# design.net
KiCad netlist of a schematic drawn in Altium Designer
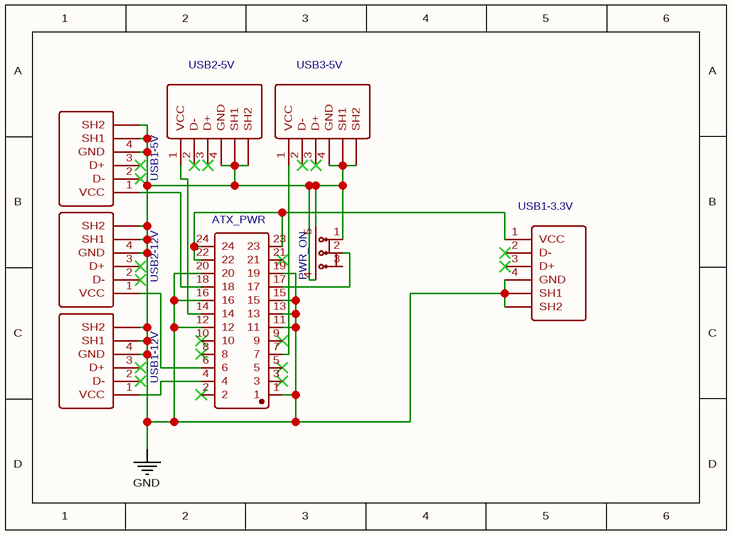
[diagram p0: 原理图.schdoc]

(export (version "E")
  (design (tool "Eeschema 10.0.6"))
  (components
    (comp (ref "ATX_PWR")
      (value "5557S-2*12P")
      (fields
        (field (name "BOM_MANUFACTURER PART") "W-5557S24P-0000")
        (field (name "BOM_SUPPLIER PART") "C169053")
        (field (name "CONTRIBUTOR") "LCSC")
      )
      (libsource (lib "altium-import") (part "root_2_5557S-2*12P_"))
    )
    (comp (ref "PWR_ON")
      (value "SS-12D02-VG4_C2998801")
      (fields
        (field (name "BOM_SUPPLIER PART") "C2998801")
        (field (name "BOM_MANUFACTURER PART") "SS-12D02-VG4")
        (field (name "CONTRIBUTOR") "lcsc")
      )
      (libsource (lib "altium-import") (part "root_3_SS-12D02-VG4_C2998801_"))
    )
    (comp (ref "USB1-3.3V")
      (value "U-USBAM04P-F001")
      (fields (field (name "BOM_SUPPLIER PART") "C2895042") (field (name "CONTRIBUTOR") "LCSC"))
      (libsource (lib "altium-import") (part "root_0_U-USBAM04P-F001_"))
    )
    (comp (ref "USB1-5V")
      (value "U-USBAM04P-F001")
      (fields (field (name "BOM_SUPPLIER PART") "C2895042") (field (name "CONTRIBUTOR") "LCSC"))
      (libsource (lib "altium-import") (part "root_2_U-USBAM04P-F001_"))
    )
    (comp (ref "USB1-12V")
      (value "U-USBAM04P-F001")
      (fields (field (name "BOM_SUPPLIER PART") "C2895042") (field (name "CONTRIBUTOR") "LCSC"))
      (libsource (lib "altium-import") (part "root_2_U-USBAM04P-F001_"))
    )
    (comp (ref "USB2-5V")
      (value "U-USBAM04P-F001")
      (fields (field (name "BOM_SUPPLIER PART") "C2895042") (field (name "CONTRIBUTOR") "LCSC"))
      (libsource (lib "altium-import") (part "root_1_U-USBAM04P-F001_"))
    )
    (comp (ref "USB2-12V")
      (value "U-USBAM04P-F001")
      (fields (field (name "BOM_SUPPLIER PART") "C2895042") (field (name "CONTRIBUTOR") "LCSC"))
      (libsource (lib "altium-import") (part "root_2_U-USBAM04P-F001_"))
    )
    (comp (ref "USB3-5V")
      (value "U-USBAM04P-F001")
      (fields (field (name "BOM_SUPPLIER PART") "C2895042") (field (name "CONTRIBUTOR") "LCSC"))
      (libsource (lib "altium-import") (part "root_1_U-USBAM04P-F001_"))
    )
  )
  (nets
    (net (code "1") (name "GND") (class "Default")
      (node (ref "ATX_PWR") (pin "1") (pinfunction "1_1") (pintype "passive"))
      (node (ref "ATX_PWR") (pin "11") (pinfunction "11_11") (pintype "passive"))
      (node (ref "ATX_PWR") (pin "12") (pinfunction "12_12") (pintype "passive"))
      (node (ref "ATX_PWR") (pin "13") (pinfunction "13_13") (pintype "passive"))
      (node (ref "ATX_PWR") (pin "15") (pinfunction "15_15") (pintype "passive"))
      (node (ref "ATX_PWR") (pin "16") (pinfunction "16_16") (pintype "passive"))
      (node (ref "ATX_PWR") (pin "19") (pinfunction "19_19") (pintype "passive"))
      (node (ref "ATX_PWR") (pin "20") (pinfunction "20_20") (pintype "passive"))
      (node (ref "PWR_ON") (pin "1") (pinfunction "1_1") (pintype "passive"))
      (node (ref "PWR_ON") (pin "4") (pinfunction "4_4") (pintype "passive"))
      (node (ref "PWR_ON") (pin "5") (pinfunction "5_5") (pintype "passive"))
      (node (ref "USB1-12V") (pin "4") (pinfunction "GND_4") (pintype "passive"))
      (node (ref "USB1-12V") (pin "SH1") (pinfunction "SH1_SH1") (pintype "passive"))
      (node (ref "USB1-12V") (pin "SH2") (pinfunction "SH2_SH2") (pintype "passive"))
      (node (ref "USB1-3.3V") (pin "4") (pinfunction "GND_4") (pintype "passive"))
      (node (ref "USB1-3.3V") (pin "SH1") (pinfunction "SH1_SH1") (pintype "passive"))
      (node (ref "USB1-3.3V") (pin "SH2") (pinfunction "SH2_SH2") (pintype "passive"))
      (node (ref "USB1-5V") (pin "4") (pinfunction "GND_4") (pintype "passive"))
      (node (ref "USB1-5V") (pin "SH1") (pinfunction "SH1_SH1") (pintype "passive"))
      (node (ref "USB1-5V") (pin "SH2") (pinfunction "SH2_SH2") (pintype "passive"))
      (node (ref "USB2-12V") (pin "4") (pinfunction "GND_4") (pintype "passive"))
      (node (ref "USB2-12V") (pin "SH1") (pinfunction "SH1_SH1") (pintype "passive"))
      (node (ref "USB2-12V") (pin "SH2") (pinfunction "SH2_SH2") (pintype "passive"))
      (node (ref "USB2-5V") (pin "4") (pinfunction "GND_4") (pintype "passive"))
      (node (ref "USB2-5V") (pin "SH1") (pinfunction "SH1_SH1") (pintype "passive"))
      (node (ref "USB2-5V") (pin "SH2") (pinfunction "SH2_SH2") (pintype "passive"))
      (node (ref "USB3-5V") (pin "4") (pinfunction "GND_4") (pintype "passive"))
      (node (ref "USB3-5V") (pin "SH1") (pinfunction "SH1_SH1") (pintype "passive"))
      (node (ref "USB3-5V") (pin "SH2") (pinfunction "SH2_SH2") (pintype "passive"))
    )
    (net (code "2") (name "Net-(ATX_PWR-Pad17)") (class "Default")
      (node (ref "ATX_PWR") (pin "17") (pinfunction "17_17") (pintype "passive"))
      (node (ref "PWR_ON") (pin "2") (pinfunction "2_2") (pintype "passive"))
    )
    (net (code "3") (name "Net-(USB1-3.3V-VCC)") (class "Default")
      (node (ref "ATX_PWR") (pin "22") (pinfunction "22_22") (pintype "passive"))
      (node (ref "ATX_PWR") (pin "23") (pinfunction "23_23") (pintype "passive"))
      (node (ref "ATX_PWR") (pin "24") (pinfunction "24_24") (pintype "passive"))
      (node (ref "USB1-3.3V") (pin "1") (pinfunction "VCC_1") (pintype "passive"))
    )
    (net (code "4") (name "Net-(USB1-5V-VCC)") (class "Default")
      (node (ref "ATX_PWR") (pin "18") (pinfunction "18_18") (pintype "passive"))
      (node (ref "USB1-5V") (pin "1") (pinfunction "VCC_1") (pintype "passive"))
    )
    (net (code "5") (name "Net-(USB1-12V-VCC)") (class "Default")
      (node (ref "ATX_PWR") (pin "4") (pinfunction "4_4") (pintype "passive"))
      (node (ref "USB1-12V") (pin "1") (pinfunction "VCC_1") (pintype "passive"))
    )
    (net (code "6") (name "Net-(USB2-5V-VCC)") (class "Default")
      (node (ref "ATX_PWR") (pin "14") (pinfunction "14_14") (pintype "passive"))
      (node (ref "USB2-5V") (pin "1") (pinfunction "VCC_1") (pintype "passive"))
    )
    (net (code "7") (name "Net-(USB2-12V-VCC)") (class "Default")
      (node (ref "ATX_PWR") (pin "6") (pinfunction "6_6") (pintype "passive"))
      (node (ref "USB2-12V") (pin "1") (pinfunction "VCC_1") (pintype "passive"))
    )
    (net (code "8") (name "Net-(USB3-5V-VCC)") (class "Default")
      (node (ref "ATX_PWR") (pin "7") (pinfunction "7_7") (pintype "passive"))
      (node (ref "USB3-5V") (pin "1") (pinfunction "VCC_1") (pintype "passive"))
    )
    (net (code "9") (name "unconnected-(ATX_PWR-Pad2)") (class "Default")
      (node (ref "ATX_PWR") (pin "2") (pinfunction "2_2") (pintype "passive+no_connect"))
    )
    (net (code "10") (name "unconnected-(ATX_PWR-Pad3)") (class "Default")
      (node (ref "ATX_PWR") (pin "3") (pinfunction "3_3") (pintype "passive+no_connect"))
    )
    (net (code "11") (name "unconnected-(ATX_PWR-Pad5)") (class "Default")
      (node (ref "ATX_PWR") (pin "5") (pinfunction "5_5") (pintype "passive+no_connect"))
    )
    (net (code "12") (name "unconnected-(ATX_PWR-Pad8)") (class "Default")
      (node (ref "ATX_PWR") (pin "8") (pinfunction "8_8") (pintype "passive+no_connect"))
    )
    (net (code "13") (name "unconnected-(ATX_PWR-Pad9)") (class "Default")
      (node (ref "ATX_PWR") (pin "9") (pinfunction "9_9") (pintype "passive+no_connect"))
    )
    (net (code "14") (name "unconnected-(ATX_PWR-Pad10)") (class "Default")
      (node (ref "ATX_PWR") (pin "10") (pinfunction "10_10") (pintype "passive+no_connect"))
    )
    (net (code "15") (name "unconnected-(ATX_PWR-Pad21)") (class "Default")
      (node (ref "ATX_PWR") (pin "21") (pinfunction "21_21") (pintype "passive+no_connect"))
    )
    (net (code "16") (name "unconnected-(PWR_ON-Pad3)") (class "Default")
      (node (ref "PWR_ON") (pin "3") (pinfunction "3_3") (pintype "passive"))
    )
    (net (code "17") (name "unconnected-(USB1-3.3V-D+-Pad3)") (class "Default")
      (node (ref "USB1-3.3V") (pin "3") (pinfunction "D+_3") (pintype "passive+no_connect"))
    )
    (net (code "18") (name "unconnected-(USB1-3.3V-D--Pad2)") (class "Default")
      (node (ref "USB1-3.3V") (pin "2") (pinfunction "D-_2") (pintype "passive+no_connect"))
    )
    (net (code "19") (name "unconnected-(USB1-5V-D+-Pad3)") (class "Default")
      (node (ref "USB1-5V") (pin "3") (pinfunction "D+_3") (pintype "passive+no_connect"))
    )
    (net (code "20") (name "unconnected-(USB1-5V-D--Pad2)") (class "Default")
      (node (ref "USB1-5V") (pin "2") (pinfunction "D-_2") (pintype "passive+no_connect"))
    )
    (net (code "21") (name "unconnected-(USB1-12V-D+-Pad3)") (class "Default")
      (node (ref "USB1-12V") (pin "3") (pinfunction "D+_3") (pintype "passive+no_connect"))
    )
    (net (code "22") (name "unconnected-(USB1-12V-D--Pad2)") (class "Default")
      (node (ref "USB1-12V") (pin "2") (pinfunction "D-_2") (pintype "passive+no_connect"))
    )
    (net (code "23") (name "unconnected-(USB2-5V-D+-Pad3)") (class "Default")
      (node (ref "USB2-5V") (pin "3") (pinfunction "D+_3") (pintype "passive+no_connect"))
    )
    (net (code "24") (name "unconnected-(USB2-5V-D--Pad2)") (class "Default")
      (node (ref "USB2-5V") (pin "2") (pinfunction "D-_2") (pintype "passive+no_connect"))
    )
    (net (code "25") (name "unconnected-(USB2-12V-D+-Pad3)") (class "Default")
      (node (ref "USB2-12V") (pin "3") (pinfunction "D+_3") (pintype "passive+no_connect"))
    )
    (net (code "26") (name "unconnected-(USB2-12V-D--Pad2)") (class "Default")
      (node (ref "USB2-12V") (pin "2") (pinfunction "D-_2") (pintype "passive+no_connect"))
    )
    (net (code "27") (name "unconnected-(USB3-5V-D+-Pad3)") (class "Default")
      (node (ref "USB3-5V") (pin "3") (pinfunction "D+_3") (pintype "passive+no_connect"))
    )
    (net (code "28") (name "unconnected-(USB3-5V-D--Pad2)") (class "Default")
      (node (ref "USB3-5V") (pin "2") (pinfunction "D-_2") (pintype "passive+no_connect"))
    )
  )
)
